# H-Bridge_L9110.net
KiCad netlist of a schematic drawn in EAGLE
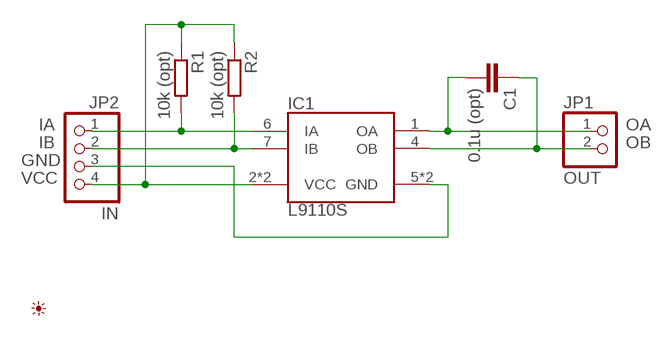
[diagram p0: schematic, sheet 1]

(export (version "E")
  (design (tool "Eeschema 10.0.6"))
  (components
    (comp (ref "C1")
      (value "0.1u (opt)")
      (footprint "eagle-import:C0805K")
      (libsource (lib "eagle-import") (part "C-EUC0805K"))
    )
    (comp (ref "IC1")
      (value "L9110S")
      (footprint "eagle-import:SO8")
      (libsource (lib "eagle-import") (part "L9110S"))
    )
    (comp (ref "JP1")
      (value "OUT")
      (footprint "eagle-import:1X02")
      (libsource (lib "eagle-import") (part "PINHD-1X2"))
    )
    (comp (ref "JP2")
      (value "IN")
      (footprint "eagle-import:1X04")
      (libsource (lib "eagle-import") (part "PINHD-1X4"))
    )
    (comp (ref "PICTO1")
      (value "PICTO_1")
      (footprint "eagle-import:PICTO_1")
      (libsource (lib "eagle-import") (part "PICTO_1"))
    )
    (comp (ref "R1")
      (value "10k (opt)")
      (footprint "eagle-import:R0603")
      (libsource (lib "eagle-import") (part "R-EU_R0603"))
    )
    (comp (ref "R2")
      (value "10k (opt)")
      (footprint "eagle-import:R0603")
      (libsource (lib "eagle-import") (part "R-EU_R0603"))
    )
  )
  (nets
    (net (code "1") (name "/GND") (class "Default")
      (node (ref "IC1") (pin "5") (pinfunction "GND_5") (pintype "power_in"))
      (node (ref "IC1") (pin "8") (pinfunction "GND_8") (pintype "power_in"))
      (node (ref "JP2") (pin "3") (pinfunction "3_3") (pintype "passive"))
    )
    (net (code "2") (name "/IA") (class "Default")
      (node (ref "IC1") (pin "6") (pinfunction "IA_6") (pintype "input"))
      (node (ref "JP2") (pin "1") (pinfunction "1_1") (pintype "passive"))
      (node (ref "R1") (pin "2") (pinfunction "2_2") (pintype "passive"))
    )
    (net (code "3") (name "/IB") (class "Default")
      (node (ref "IC1") (pin "7") (pinfunction "IB_7") (pintype "input"))
      (node (ref "JP2") (pin "2") (pinfunction "2_2") (pintype "passive"))
      (node (ref "R2") (pin "2") (pinfunction "2_2") (pintype "passive"))
    )
    (net (code "4") (name "/OA") (class "Default")
      (node (ref "C1") (pin "2") (pinfunction "2_2") (pintype "passive"))
      (node (ref "IC1") (pin "1") (pinfunction "OA_1") (pintype "output"))
      (node (ref "JP1") (pin "1") (pinfunction "1_1") (pintype "passive"))
    )
    (net (code "5") (name "/OB") (class "Default")
      (node (ref "C1") (pin "1") (pinfunction "1_1") (pintype "passive"))
      (node (ref "IC1") (pin "4") (pinfunction "OB_4") (pintype "output"))
      (node (ref "JP1") (pin "2") (pinfunction "2_2") (pintype "passive"))
    )
    (net (code "6") (name "/VCC") (class "Default")
      (node (ref "IC1") (pin "2") (pinfunction "VCC_2") (pintype "power_in"))
      (node (ref "IC1") (pin "3") (pinfunction "VCC_3") (pintype "power_in"))
      (node (ref "JP2") (pin "4") (pinfunction "4_4") (pintype "passive"))
      (node (ref "R1") (pin "1") (pinfunction "1_1") (pintype "passive"))
      (node (ref "R2") (pin "1") (pinfunction "1_1") (pintype "passive"))
    )
  )
)
